# Commutation.net
KiCad netlist of a schematic drawn in Altium Designer
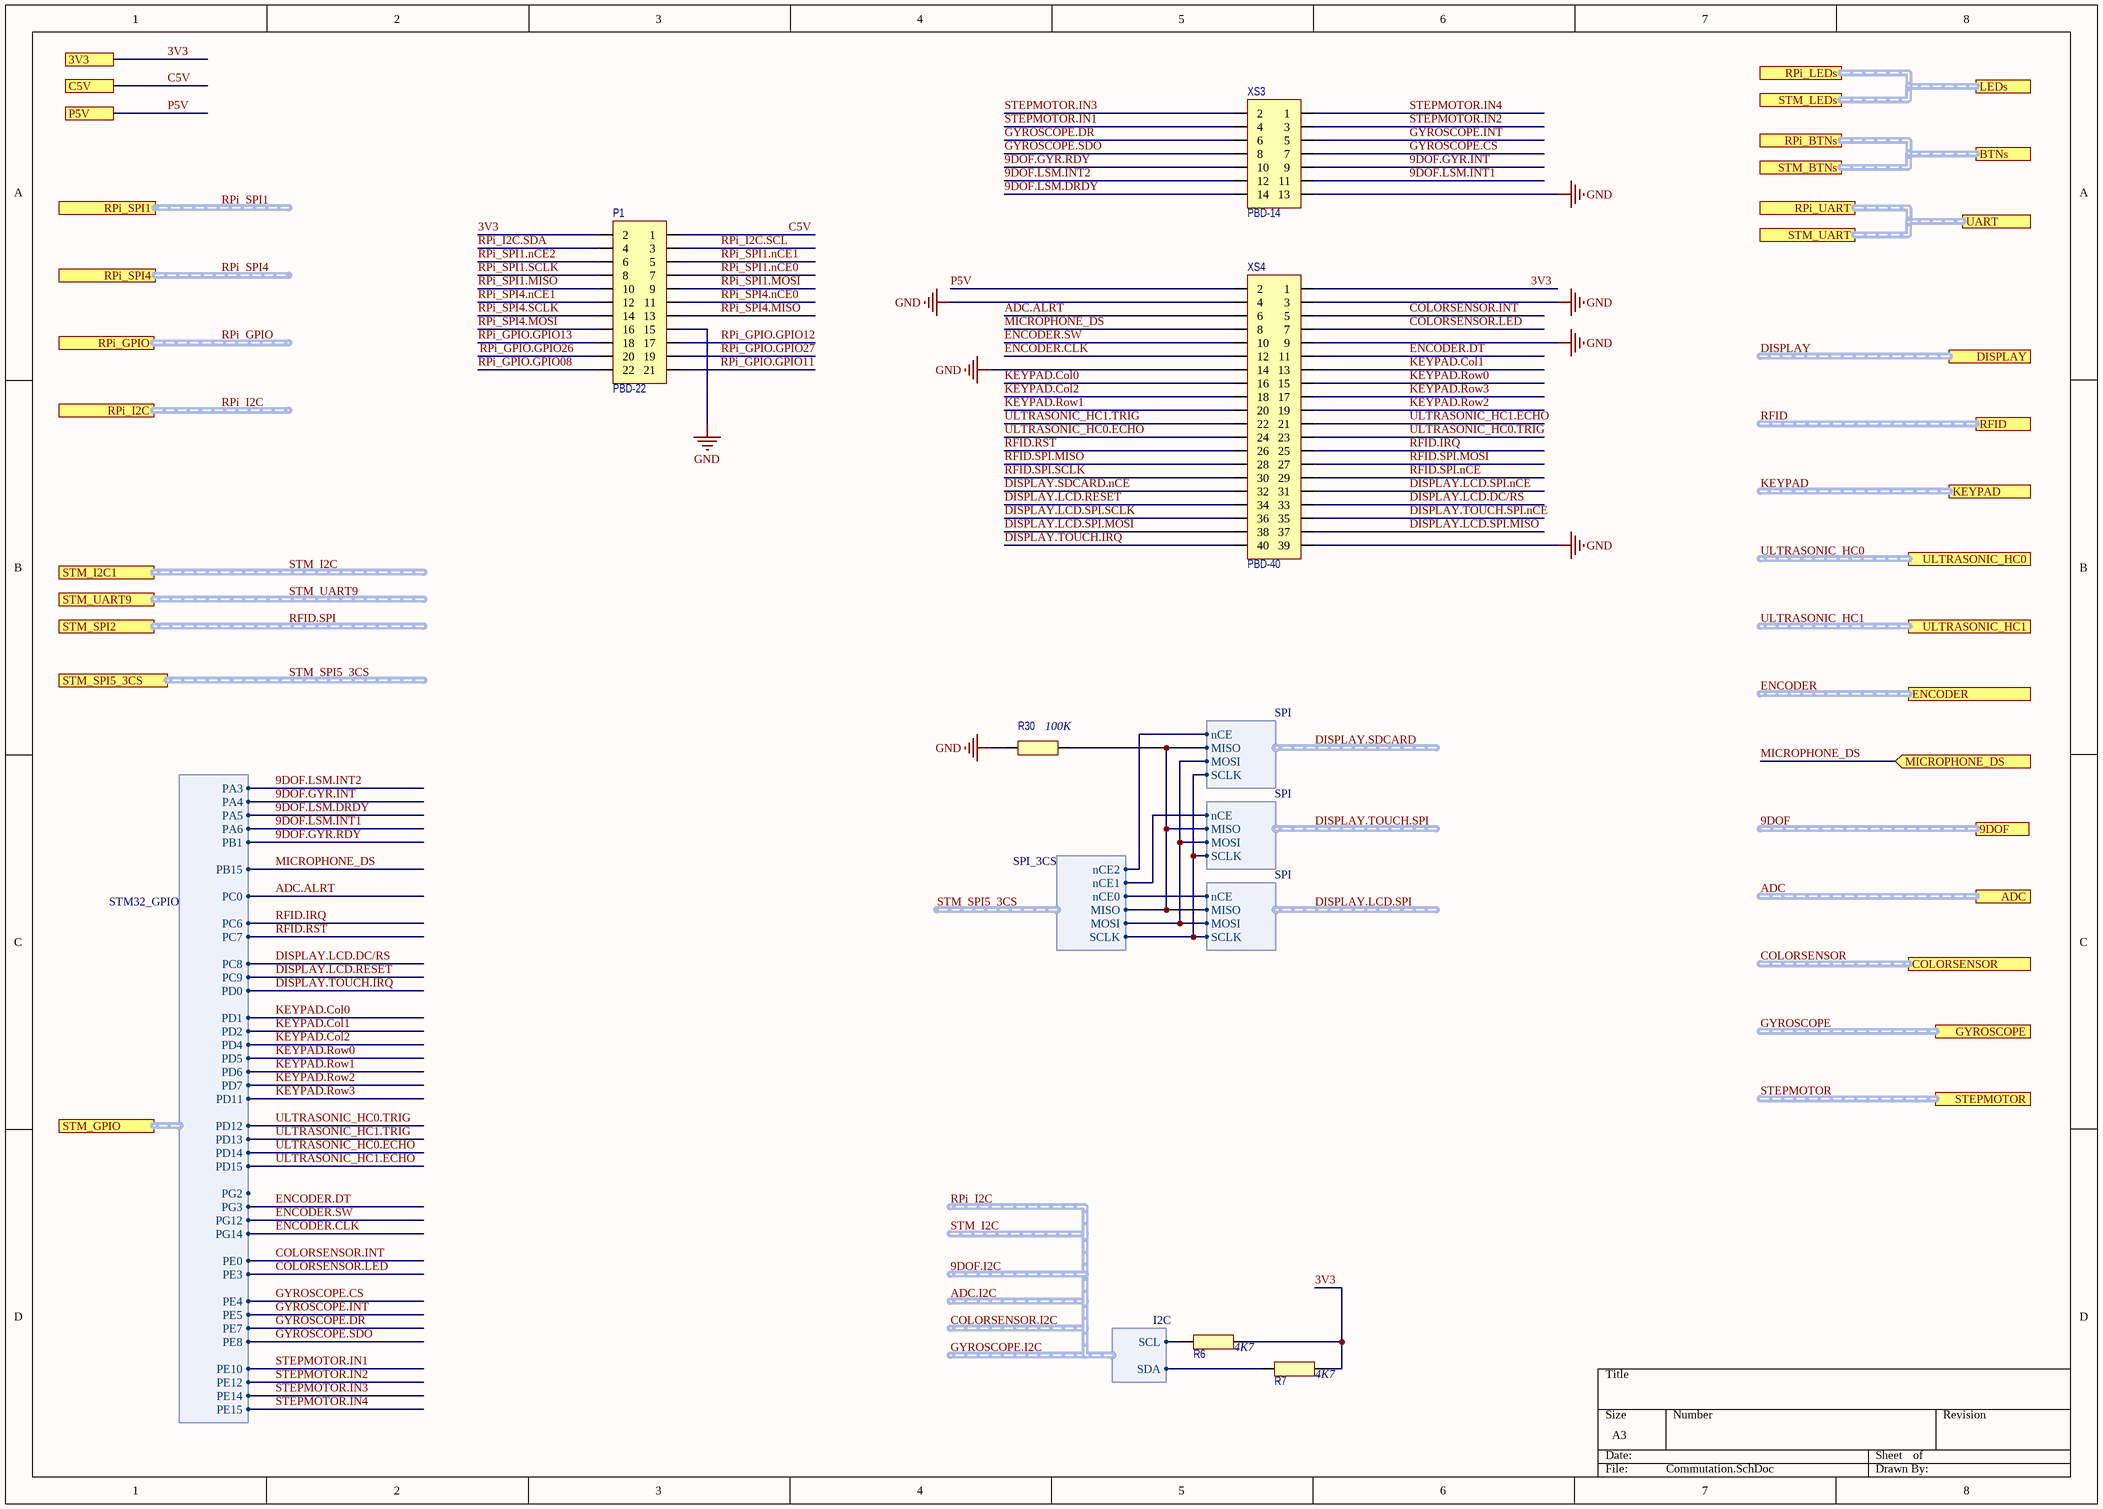
[diagram p0: Commutation.SchDoc]

(export (version "E")
  (design (tool "Eeschema 10.0.6"))
  (components
    (comp (ref "P1") (value "PBD-22") (footprint "PBD-22") (libsource (lib "my_AP_lib_sch") (part "PBD-22")))
    (comp (ref "R6")
      (value "4K7")
      (footprint "R0805")
      (fields (field (name "Comment") "R0805"))
      (libsource (lib "my_AP_lib_sch") (part "R0805"))
    )
    (comp (ref "R7")
      (value "4K7")
      (footprint "R0805")
      (fields (field (name "Comment") "R0805"))
      (libsource (lib "my_AP_lib_sch") (part "R0805"))
    )
    (comp (ref "R30")
      (value "100K")
      (footprint "R0805")
      (fields (field (name "Comment") "R0805"))
      (libsource (lib "") (part "R0805_1"))
    )
    (comp (ref "XS3") (value "PBD-14") (footprint "PBD-14") (libsource (lib "my_AP_lib_sch") (part "PBD-14")))
    (comp (ref "XS4") (value "PBD-40") (footprint "PBD-40") (libsource (lib "my_AP_lib_sch") (part "PBD-40")))
  )
  (nets
    (net (code "27") (name "/3V3") (class "Default")
      (node (ref "P1") (pin "2") (pinfunction "2_2") (pintype "passive"))
      (node (ref "R6") (pin "1") (pinfunction "1_1") (pintype "passive"))
      (node (ref "R7") (pin "1") (pinfunction "1_1") (pintype "passive"))
      (node (ref "XS4") (pin "1") (pinfunction "1_1") (pintype "passive"))
    )
    (net (code "28") (name "/9DOF.GYR.INT") (class "Default")
      (node (ref "XS3") (pin "9") (pinfunction "9_9") (pintype "passive"))
    )
    (net (code "29") (name "/9DOF.GYR.RDY") (class "Default")
      (node (ref "XS3") (pin "10") (pinfunction "10_10") (pintype "passive"))
    )
    (net (code "30") (name "/9DOF.LSM.DRDY") (class "Default")
      (node (ref "XS3") (pin "14") (pinfunction "14_14") (pintype "passive"))
    )
    (net (code "31") (name "/9DOF.LSM.INT1") (class "Default")
      (node (ref "XS3") (pin "11") (pinfunction "11_11") (pintype "passive"))
    )
    (net (code "32") (name "/9DOF.LSM.INT2") (class "Default")
      (node (ref "XS3") (pin "12") (pinfunction "12_12") (pintype "passive"))
    )
    (net (code "33") (name "/ADC.ALRT") (class "Default")
      (node (ref "XS4") (pin "6") (pinfunction "6_6") (pintype "passive"))
    )
    (net (code "35") (name "/C5V") (class "Default")
      (node (ref "P1") (pin "1") (pinfunction "1_1") (pintype "passive"))
    )
    (net (code "36") (name "/COLORSENSOR.INT") (class "Default")
      (node (ref "XS4") (pin "5") (pinfunction "5_5") (pintype "passive"))
    )
    (net (code "37") (name "/COLORSENSOR.LED") (class "Default")
      (node (ref "XS4") (pin "7") (pinfunction "7_7") (pintype "passive"))
    )
    (net (code "38") (name "/DISPLAY.LCD.DC{slash}RS") (class "Default")
      (node (ref "XS4") (pin "33") (pinfunction "33_33") (pintype "passive"))
    )
    (net (code "39") (name "/DISPLAY.LCD.RESET") (class "Default")
      (node (ref "XS4") (pin "34") (pinfunction "34_34") (pintype "passive"))
    )
    (net (code "40") (name "/DISPLAY.LCD.SPI.MISO") (class "Default")
      (node (ref "XS4") (pin "37") (pinfunction "37_37") (pintype "passive"))
    )
    (net (code "41") (name "/DISPLAY.LCD.SPI.MOSI") (class "Default")
      (node (ref "XS4") (pin "38") (pinfunction "38_38") (pintype "passive"))
    )
    (net (code "42") (name "/DISPLAY.LCD.SPI.SCLK") (class "Default")
      (node (ref "XS4") (pin "36") (pinfunction "36_36") (pintype "passive"))
    )
    (net (code "43") (name "/DISPLAY.LCD.SPI.nCE") (class "Default")
      (node (ref "XS4") (pin "31") (pinfunction "31_31") (pintype "passive"))
    )
    (net (code "45") (name "/DISPLAY.SDCARD.nCE") (class "Default")
      (node (ref "XS4") (pin "32") (pinfunction "32_32") (pintype "passive"))
    )
    (net (code "47") (name "/DISPLAY.TOUCH.IRQ") (class "Default")
      (node (ref "XS4") (pin "40") (pinfunction "40_40") (pintype "passive"))
    )
    (net (code "48") (name "/DISPLAY.TOUCH.SPI.nCE") (class "Default")
      (node (ref "XS4") (pin "35") (pinfunction "35_35") (pintype "passive"))
    )
    (net (code "50") (name "/ENCODER.CLK") (class "Default")
      (node (ref "XS4") (pin "12") (pinfunction "12_12") (pintype "passive"))
    )
    (net (code "51") (name "/ENCODER.DT") (class "Default")
      (node (ref "XS4") (pin "11") (pinfunction "11_11") (pintype "passive"))
    )
    (net (code "52") (name "/ENCODER.SW") (class "Default")
      (node (ref "XS4") (pin "10") (pinfunction "10_10") (pintype "passive"))
    )
    (net (code "53") (name "/GYROSCOPE.CS") (class "Default")
      (node (ref "XS3") (pin "7") (pinfunction "7_7") (pintype "passive"))
    )
    (net (code "54") (name "/GYROSCOPE.DR") (class "Default")
      (node (ref "XS3") (pin "6") (pinfunction "6_6") (pintype "passive"))
    )
    (net (code "56") (name "/GYROSCOPE.INT") (class "Default")
      (node (ref "XS3") (pin "5") (pinfunction "5_5") (pintype "passive"))
    )
    (net (code "57") (name "/GYROSCOPE.SDO") (class "Default")
      (node (ref "XS3") (pin "8") (pinfunction "8_8") (pintype "passive"))
    )
    (net (code "58") (name "/KEYPAD.Col0") (class "Default")
      (node (ref "XS4") (pin "16") (pinfunction "16_16") (pintype "passive"))
    )
    (net (code "59") (name "/KEYPAD.Col1") (class "Default")
      (node (ref "XS4") (pin "13") (pinfunction "13_13") (pintype "passive"))
    )
    (net (code "60") (name "/KEYPAD.Col2") (class "Default")
      (node (ref "XS4") (pin "18") (pinfunction "18_18") (pintype "passive"))
    )
    (net (code "61") (name "/KEYPAD.Row0") (class "Default")
      (node (ref "XS4") (pin "15") (pinfunction "15_15") (pintype "passive"))
    )
    (net (code "62") (name "/KEYPAD.Row1") (class "Default")
      (node (ref "XS4") (pin "20") (pinfunction "20_20") (pintype "passive"))
    )
    (net (code "63") (name "/KEYPAD.Row2") (class "Default")
      (node (ref "XS4") (pin "19") (pinfunction "19_19") (pintype "passive"))
    )
    (net (code "64") (name "/KEYPAD.Row3") (class "Default")
      (node (ref "XS4") (pin "17") (pinfunction "17_17") (pintype "passive"))
    )
    (net (code "66") (name "/MICROPHONE_DS") (class "Default")
      (node (ref "XS4") (pin "8") (pinfunction "8_8") (pintype "passive"))
    )
    (net (code "67") (name "/MISO") (class "Default")
      (node (ref "R30") (pin "2") (pinfunction "2_2") (pintype "passive"))
    )
    (net (code "69") (name "/P5V") (class "Default")
      (node (ref "XS4") (pin "2") (pinfunction "2_2") (pintype "passive"))
    )
    (net (code "70") (name "/RFID.IRQ") (class "Default")
      (node (ref "XS4") (pin "25") (pinfunction "25_25") (pintype "passive"))
    )
    (net (code "71") (name "/RFID.RST") (class "Default")
      (node (ref "XS4") (pin "26") (pinfunction "26_26") (pintype "passive"))
    )
    (net (code "72") (name "/RFID.SPI.MISO") (class "Default")
      (node (ref "XS4") (pin "28") (pinfunction "28_28") (pintype "passive"))
    )
    (net (code "73") (name "/RFID.SPI.MOSI") (class "Default")
      (node (ref "XS4") (pin "27") (pinfunction "27_27") (pintype "passive"))
    )
    (net (code "74") (name "/RFID.SPI.SCLK") (class "Default")
      (node (ref "XS4") (pin "30") (pinfunction "30_30") (pintype "passive"))
    )
    (net (code "75") (name "/RFID.SPI.nCE") (class "Default")
      (node (ref "XS4") (pin "29") (pinfunction "29_29") (pintype "passive"))
    )
    (net (code "76") (name "/RPi_GPIO.GPIO08") (class "Default")
      (node (ref "P1") (pin "22") (pinfunction "22_22") (pintype "passive"))
    )
    (net (code "77") (name "/RPi_GPIO.GPIO11") (class "Default")
      (node (ref "P1") (pin "21") (pinfunction "21_21") (pintype "passive"))
    )
    (net (code "78") (name "/RPi_GPIO.GPIO12") (class "Default")
      (node (ref "P1") (pin "17") (pinfunction "17_17") (pintype "passive"))
    )
    (net (code "79") (name "/RPi_GPIO.GPIO13") (class "Default")
      (node (ref "P1") (pin "18") (pinfunction "18_18") (pintype "passive"))
    )
    (net (code "80") (name "/RPi_GPIO.GPIO26") (class "Default")
      (node (ref "P1") (pin "20") (pinfunction "20_20") (pintype "passive"))
    )
    (net (code "81") (name "/RPi_GPIO.GPIO27") (class "Default")
      (node (ref "P1") (pin "19") (pinfunction "19_19") (pintype "passive"))
    )
    (net (code "82") (name "/RPi_I2C.SCL") (class "Default")
      (node (ref "P1") (pin "3") (pinfunction "3_3") (pintype "passive"))
    )
    (net (code "83") (name "/RPi_I2C.SDA") (class "Default")
      (node (ref "P1") (pin "4") (pinfunction "4_4") (pintype "passive"))
    )
    (net (code "84") (name "/RPi_SPI1.MISO") (class "Default")
      (node (ref "P1") (pin "10") (pinfunction "10_10") (pintype "passive"))
    )
    (net (code "85") (name "/RPi_SPI1.MOSI") (class "Default")
      (node (ref "P1") (pin "9") (pinfunction "9_9") (pintype "passive"))
    )
    (net (code "86") (name "/RPi_SPI1.SCLK") (class "Default")
      (node (ref "P1") (pin "8") (pinfunction "8_8") (pintype "passive"))
    )
    (net (code "87") (name "/RPi_SPI1.nCE0") (class "Default")
      (node (ref "P1") (pin "7") (pinfunction "7_7") (pintype "passive"))
    )
    (net (code "88") (name "/RPi_SPI1.nCE1") (class "Default")
      (node (ref "P1") (pin "5") (pinfunction "5_5") (pintype "passive"))
    )
    (net (code "89") (name "/RPi_SPI1.nCE2") (class "Default")
      (node (ref "P1") (pin "6") (pinfunction "6_6") (pintype "passive"))
    )
    (net (code "90") (name "/RPi_SPI4.MISO") (class "Default")
      (node (ref "P1") (pin "13") (pinfunction "13_13") (pintype "passive"))
    )
    (net (code "91") (name "/RPi_SPI4.MOSI") (class "Default")
      (node (ref "P1") (pin "16") (pinfunction "16_16") (pintype "passive"))
    )
    (net (code "92") (name "/RPi_SPI4.SCLK") (class "Default")
      (node (ref "P1") (pin "14") (pinfunction "14_14") (pintype "passive"))
    )
    (net (code "93") (name "/RPi_SPI4.nCE0") (class "Default")
      (node (ref "P1") (pin "11") (pinfunction "11_11") (pintype "passive"))
    )
    (net (code "94") (name "/RPi_SPI4.nCE1") (class "Default")
      (node (ref "P1") (pin "12") (pinfunction "12_12") (pintype "passive"))
    )
    (net (code "96") (name "/SCL") (class "Default")
      (node (ref "R6") (pin "2") (pinfunction "2_2") (pintype "passive"))
    )
    (net (code "98") (name "/SDA") (class "Default")
      (node (ref "R7") (pin "2") (pinfunction "2_2") (pintype "passive"))
    )
    (net (code "99") (name "/STEPMOTOR.IN1") (class "Default")
      (node (ref "XS3") (pin "4") (pinfunction "4_4") (pintype "passive"))
    )
    (net (code "100") (name "/STEPMOTOR.IN2") (class "Default")
      (node (ref "XS3") (pin "3") (pinfunction "3_3") (pintype "passive"))
    )
    (net (code "101") (name "/STEPMOTOR.IN3") (class "Default")
      (node (ref "XS3") (pin "2") (pinfunction "2_2") (pintype "passive"))
    )
    (net (code "102") (name "/STEPMOTOR.IN4") (class "Default")
      (node (ref "XS3") (pin "1") (pinfunction "1_1") (pintype "passive"))
    )
    (net (code "104") (name "/ULTRASONIC_HC0.ECHO") (class "Default")
      (node (ref "XS4") (pin "24") (pinfunction "24_24") (pintype "passive"))
    )
    (net (code "105") (name "/ULTRASONIC_HC0.TRIG") (class "Default")
      (node (ref "XS4") (pin "23") (pinfunction "23_23") (pintype "passive"))
    )
    (net (code "106") (name "/ULTRASONIC_HC1.ECHO") (class "Default")
      (node (ref "XS4") (pin "21") (pinfunction "21_21") (pintype "passive"))
    )
    (net (code "107") (name "/ULTRASONIC_HC1.TRIG") (class "Default")
      (node (ref "XS4") (pin "22") (pinfunction "22_22") (pintype "passive"))
    )
    (net (code "128") (name "GND") (class "Default")
      (node (ref "P1") (pin "15") (pinfunction "15_15") (pintype "passive"))
      (node (ref "R30") (pin "1") (pinfunction "1_1") (pintype "passive"))
      (node (ref "XS3") (pin "13") (pinfunction "13_13") (pintype "passive"))
      (node (ref "XS4") (pin "14") (pinfunction "14_14") (pintype "passive"))
      (node (ref "XS4") (pin "3") (pinfunction "3_3") (pintype "passive"))
      (node (ref "XS4") (pin "39") (pinfunction "39_39") (pintype "passive"))
      (node (ref "XS4") (pin "4") (pinfunction "4_4") (pintype "passive"))
      (node (ref "XS4") (pin "9") (pinfunction "9_9") (pintype "passive"))
    )
  )
)
